# rc360detector.net
KiCad netlist of a schematic drawn in EAGLE
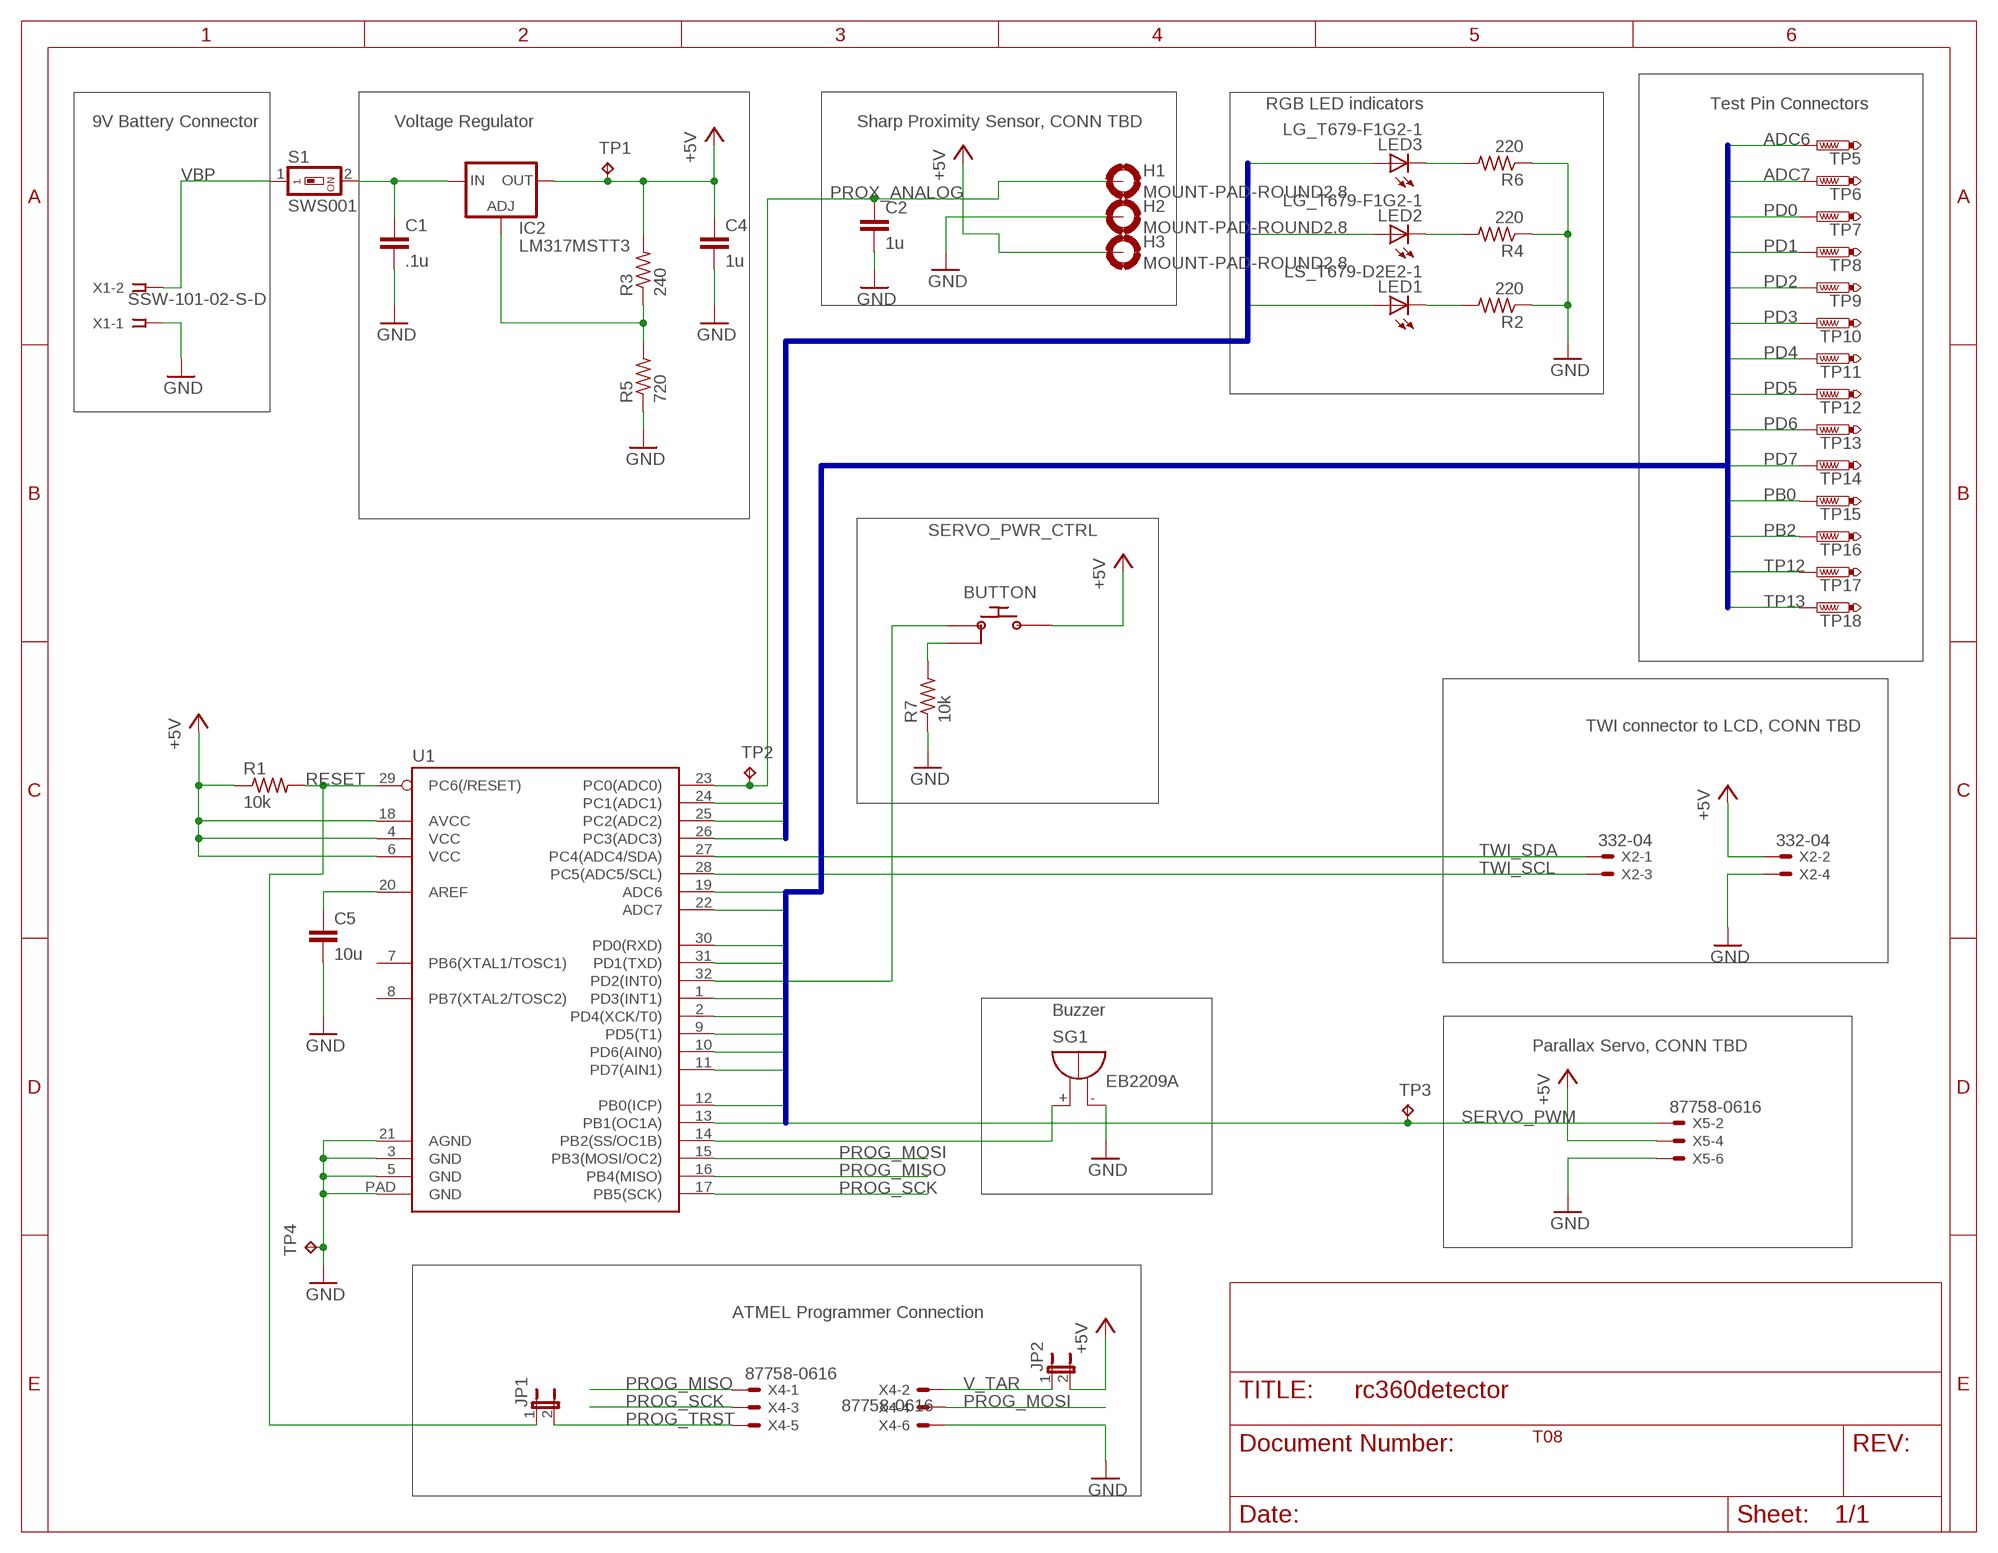
[diagram p0: schematic, sheet 1]

(export (version "E")
  (design (tool "Eeschema 10.0.6"))
  (components
    (comp (ref "BUTTON")
      (value "PR141C")
      (footprint "eagle-import:3_THROUGH_HOLE")
      (libsource (lib "eagle-import") (part "PR141C"))
    )
    (comp (ref "C1")
      (value ".1u")
      (footprint "eagle-import:C0603")
      (libsource (lib "eagle-import") (part "C-EUC0603"))
    )
    (comp (ref "C2")
      (value "1u")
      (footprint "eagle-import:C0805")
      (libsource (lib "eagle-import") (part "C-EUC0805"))
    )
    (comp (ref "C4")
      (value "1u")
      (footprint "eagle-import:C0603")
      (libsource (lib "eagle-import") (part "C-EUC0603"))
    )
    (comp (ref "C5")
      (value "10u")
      (footprint "eagle-import:C0603")
      (libsource (lib "eagle-import") (part "C-EUC0603"))
    )
    (comp (ref "H1")
      (value "MOUNT-PAD-ROUND2.8")
      (footprint "eagle-import:2,8-PAD")
      (libsource (lib "eagle-import") (part "MOUNT-PAD-ROUND2.8"))
    )
    (comp (ref "H2")
      (value "MOUNT-PAD-ROUND2.8")
      (footprint "eagle-import:2,8-PAD")
      (libsource (lib "eagle-import") (part "MOUNT-PAD-ROUND2.8"))
    )
    (comp (ref "H3")
      (value "MOUNT-PAD-ROUND2.8")
      (footprint "eagle-import:2,8-PAD")
      (libsource (lib "eagle-import") (part "MOUNT-PAD-ROUND2.8"))
    )
    (comp (ref "IC2")
      (value "LM317MSTT3")
      (footprint "eagle-import:SOT223")
      (libsource (lib "eagle-import") (part "LM317?MSTT3"))
    )
    (comp (ref "JP1")
      (value "JP1E")
      (footprint "eagle-import:JP1")
      (libsource (lib "eagle-import") (part "JP1E"))
    )
    (comp (ref "JP2")
      (value "JP1E")
      (footprint "eagle-import:JP1")
      (libsource (lib "eagle-import") (part "JP1E"))
    )
    (comp (ref "LED1")
      (value "LS_T679-D2E2-1")
      (footprint "eagle-import:PLCC2")
      (libsource (lib "eagle-import") (part "_T679-?-1D2E2LS"))
    )
    (comp (ref "LED2")
      (value "LG_T679-F1G2-1")
      (footprint "eagle-import:PLCC2")
      (libsource (lib "eagle-import") (part "_T679-?-1F1G2LG"))
    )
    (comp (ref "LED3")
      (value "LG_T679-F1G2-1")
      (footprint "eagle-import:PLCC2")
      (libsource (lib "eagle-import") (part "_T679-?-1F1G2LG"))
    )
    (comp (ref "R1")
      (value "10k")
      (footprint "eagle-import:R0603")
      (libsource (lib "eagle-import") (part "R-US_R0603"))
    )
    (comp (ref "R2")
      (value "220")
      (footprint "eagle-import:R0805")
      (libsource (lib "eagle-import") (part "R-US_R0805"))
    )
    (comp (ref "R3")
      (value "240")
      (footprint "eagle-import:R0603")
      (libsource (lib "eagle-import") (part "R-US_R0603"))
    )
    (comp (ref "R4")
      (value "220")
      (footprint "eagle-import:R0805")
      (libsource (lib "eagle-import") (part "R-US_R0805"))
    )
    (comp (ref "R5")
      (value "720")
      (footprint "eagle-import:R0603")
      (libsource (lib "eagle-import") (part "R-US_R0603"))
    )
    (comp (ref "R6")
      (value "220")
      (footprint "eagle-import:R0805")
      (libsource (lib "eagle-import") (part "R-US_R0805"))
    )
    (comp (ref "R7")
      (value "10k")
      (footprint "eagle-import:R0805")
      (libsource (lib "eagle-import") (part "R-US_R0805"))
    )
    (comp (ref "S1")
      (value "SWS001")
      (footprint "eagle-import:SMS-001")
      (libsource (lib "eagle-import") (part "SWS001"))
    )
    (comp (ref "SG1")
      (value "EB2209A")
      (footprint "eagle-import:EB2209A")
      (libsource (lib "eagle-import") (part "EB2209A"))
    )
    (comp (ref "TP1")
      (value "TPPAD1-17")
      (footprint "eagle-import:P1-17")
      (libsource (lib "eagle-import") (part "TPPAD1-17"))
    )
    (comp (ref "TP2")
      (value "TPPAD1-17")
      (footprint "eagle-import:P1-17")
      (libsource (lib "eagle-import") (part "TPPAD1-17"))
    )
    (comp (ref "TP3")
      (value "TPPAD1-17")
      (footprint "eagle-import:P1-17")
      (libsource (lib "eagle-import") (part "TPPAD1-17"))
    )
    (comp (ref "TP4")
      (value "TPPAD1-17")
      (footprint "eagle-import:P1-17")
      (libsource (lib "eagle-import") (part "TPPAD1-17"))
    )
    (comp (ref "TP5")
      (value "PTR1PAD1-20")
      (footprint "eagle-import:P1-20")
      (libsource (lib "eagle-import") (part "PTR1PAD1-20"))
    )
    (comp (ref "TP6")
      (value "PTR1PAD1-20")
      (footprint "eagle-import:P1-20")
      (libsource (lib "eagle-import") (part "PTR1PAD1-20"))
    )
    (comp (ref "TP7")
      (value "PTR1PAD1-20")
      (footprint "eagle-import:P1-20")
      (libsource (lib "eagle-import") (part "PTR1PAD1-20"))
    )
    (comp (ref "TP8")
      (value "PTR1PAD1-20")
      (footprint "eagle-import:P1-20")
      (libsource (lib "eagle-import") (part "PTR1PAD1-20"))
    )
    (comp (ref "TP9")
      (value "PTR1PAD1-20")
      (footprint "eagle-import:P1-20")
      (libsource (lib "eagle-import") (part "PTR1PAD1-20"))
    )
    (comp (ref "TP10")
      (value "PTR1PAD1-20")
      (footprint "eagle-import:P1-20")
      (libsource (lib "eagle-import") (part "PTR1PAD1-20"))
    )
    (comp (ref "TP11")
      (value "PTR1PAD1-20")
      (footprint "eagle-import:P1-20")
      (libsource (lib "eagle-import") (part "PTR1PAD1-20"))
    )
    (comp (ref "TP12")
      (value "PTR1PAD1-20")
      (footprint "eagle-import:P1-20")
      (libsource (lib "eagle-import") (part "PTR1PAD1-20"))
    )
    (comp (ref "TP13")
      (value "PTR1PAD1-20")
      (footprint "eagle-import:P1-20")
      (libsource (lib "eagle-import") (part "PTR1PAD1-20"))
    )
    (comp (ref "TP14")
      (value "PTR1PAD1-20")
      (footprint "eagle-import:P1-20")
      (libsource (lib "eagle-import") (part "PTR1PAD1-20"))
    )
    (comp (ref "TP15")
      (value "PTR1PAD1-20")
      (footprint "eagle-import:P1-20")
      (libsource (lib "eagle-import") (part "PTR1PAD1-20"))
    )
    (comp (ref "TP16")
      (value "PTR1PAD1-20")
      (footprint "eagle-import:P1-20")
      (libsource (lib "eagle-import") (part "PTR1PAD1-20"))
    )
    (comp (ref "TP17")
      (value "PTR1PAD1-20")
      (footprint "eagle-import:P1-20")
      (libsource (lib "eagle-import") (part "PTR1PAD1-20"))
    )
    (comp (ref "TP18")
      (value "PTR1PAD1-20")
      (footprint "eagle-import:P1-20")
      (libsource (lib "eagle-import") (part "PTR1PAD1-20"))
    )
    (comp (ref "U1")
      (value "ATMEGA328P_MLFMLF32")
      (footprint "eagle-import:MLF32-PAD")
      (libsource (lib "eagle-import") (part "ATMEGA328P_MLFMLF32"))
    )
    (comp (ref "X1")
      (value "SSW-101-02-S-D")
      (footprint "eagle-import:SSW-101-02-S-D")
      (libsource (lib "eagle-import") (part "SSW-101-02-S-D"))
    )
    (comp (ref "X2")
      (value "332-04")
      (footprint "eagle-import:332-04")
      (libsource (lib "eagle-import") (part "332-04"))
    )
    (comp (ref "X4")
      (value "87758-0616")
      (footprint "eagle-import:87758-0616")
      (libsource (lib "eagle-import") (part "87758-0616"))
    )
    (comp (ref "X5")
      (value "87758-0616")
      (footprint "eagle-import:87758-0616")
      (libsource (lib "eagle-import") (part "87758-0616"))
    )
  )
  (nets
    (net (code "1") (name "+5V") (class "Default")
      (node (ref "BUTTON") (pin "P$3") (pinfunction "OUT_P$3") (pintype "bidirectional"))
      (node (ref "C4") (pin "1") (pinfunction "1_1") (pintype "passive"))
      (node (ref "H3") (pin "B2,8") (pinfunction "MOUNT_B2,8") (pintype "passive"))
      (node (ref "IC2") (pin "4") (pinfunction "OUT_4") (pintype "passive"))
      (node (ref "JP2") (pin "2") (pinfunction "2_2") (pintype "passive"))
      (node (ref "R1") (pin "1") (pinfunction "1_1") (pintype "passive"))
      (node (ref "R3") (pin "2") (pinfunction "2_2") (pintype "passive"))
      (node (ref "TP1") (pin "TP") (pinfunction "TP_TP") (pintype "input"))
      (node (ref "U1") (pin "18") (pinfunction "AVCC_18") (pintype "bidirectional"))
      (node (ref "U1") (pin "4") (pinfunction "VCC_4") (pintype "bidirectional"))
      (node (ref "U1") (pin "6") (pinfunction "VCC_6") (pintype "bidirectional"))
      (node (ref "X2") (pin "2") (pinfunction "S_2") (pintype "passive"))
      (node (ref "X5") (pin "4") (pinfunction "S_4") (pintype "passive"))
    )
    (net (code "2") (name "/ADC6") (class "Default")
      (node (ref "TP5") (pin "TP") (pinfunction "TP_TP") (pintype "input"))
      (node (ref "U1") (pin "19") (pinfunction "ADC6_19") (pintype "bidirectional"))
    )
    (net (code "3") (name "/ADC7") (class "Default")
      (node (ref "TP6") (pin "TP") (pinfunction "TP_TP") (pintype "input"))
    )
    (net (code "4") (name "/LED0") (class "Default")
      (node (ref "LED1") (pin "A") (pinfunction "A_A") (pintype "passive"))
      (node (ref "U1") (pin "24") (pinfunction "PC1(ADC1)_24") (pintype "bidirectional"))
    )
    (net (code "5") (name "/LED1") (class "Default")
      (node (ref "LED2") (pin "A") (pinfunction "A_A") (pintype "passive"))
      (node (ref "U1") (pin "25") (pinfunction "PC2(ADC2)_25") (pintype "bidirectional"))
    )
    (net (code "6") (name "/LED2") (class "Default")
      (node (ref "LED3") (pin "A") (pinfunction "A_A") (pintype "passive"))
      (node (ref "U1") (pin "26") (pinfunction "PC3(ADC3)_26") (pintype "bidirectional"))
    )
    (net (code "7") (name "/PB0") (class "Default")
      (node (ref "TP15") (pin "TP") (pinfunction "TP_TP") (pintype "input"))
    )
    (net (code "8") (name "/PB2") (class "Default")
      (node (ref "TP16") (pin "TP") (pinfunction "TP_TP") (pintype "input"))
    )
    (net (code "9") (name "/PD0") (class "Default")
      (node (ref "TP7") (pin "TP") (pinfunction "TP_TP") (pintype "input"))
    )
    (net (code "10") (name "/PD1") (class "Default")
      (node (ref "TP8") (pin "TP") (pinfunction "TP_TP") (pintype "input"))
    )
    (net (code "11") (name "/PD2") (class "Default")
      (node (ref "TP9") (pin "TP") (pinfunction "TP_TP") (pintype "input"))
    )
    (net (code "12") (name "/PD3") (class "Default")
      (node (ref "TP10") (pin "TP") (pinfunction "TP_TP") (pintype "input"))
    )
    (net (code "13") (name "/PD4") (class "Default")
      (node (ref "TP11") (pin "TP") (pinfunction "TP_TP") (pintype "input"))
    )
    (net (code "14") (name "/PD5") (class "Default")
      (node (ref "TP12") (pin "TP") (pinfunction "TP_TP") (pintype "input"))
    )
    (net (code "15") (name "/PD6") (class "Default")
      (node (ref "TP13") (pin "TP") (pinfunction "TP_TP") (pintype "input"))
    )
    (net (code "16") (name "/PD7") (class "Default")
      (node (ref "TP14") (pin "TP") (pinfunction "TP_TP") (pintype "input"))
    )
    (net (code "17") (name "/PROG_MISO") (class "Default")
      (node (ref "U1") (pin "16") (pinfunction "PB4(MISO)_16") (pintype "bidirectional"))
      (node (ref "X4") (pin "1") (pinfunction "S_1") (pintype "passive"))
    )
    (net (code "18") (name "/PROG_MOSI") (class "Default")
      (node (ref "U1") (pin "15") (pinfunction "PB3(MOSI/OC2)_15") (pintype "bidirectional"))
      (node (ref "X4") (pin "4") (pinfunction "S_4") (pintype "passive"))
    )
    (net (code "19") (name "/PROG_SCK") (class "Default")
      (node (ref "U1") (pin "17") (pinfunction "PB5(SCK)_17") (pintype "bidirectional"))
      (node (ref "X4") (pin "3") (pinfunction "S_3") (pintype "passive"))
    )
    (net (code "20") (name "/PROG_TRST") (class "Default")
      (node (ref "JP1") (pin "2") (pinfunction "2_2") (pintype "passive"))
      (node (ref "X4") (pin "5") (pinfunction "S_5") (pintype "passive"))
    )
    (net (code "21") (name "/PROX_ANALOG") (class "Default")
      (node (ref "C2") (pin "1") (pinfunction "1_1") (pintype "passive"))
      (node (ref "H1") (pin "B2,8") (pinfunction "MOUNT_B2,8") (pintype "passive"))
      (node (ref "TP2") (pin "TP") (pinfunction "TP_TP") (pintype "input"))
      (node (ref "U1") (pin "23") (pinfunction "PC0(ADC0)_23") (pintype "bidirectional"))
    )
    (net (code "22") (name "/RESET") (class "Default")
      (node (ref "JP1") (pin "1") (pinfunction "1_1") (pintype "passive"))
      (node (ref "R1") (pin "2") (pinfunction "2_2") (pintype "passive"))
      (node (ref "U1") (pin "29") (pinfunction "PC6(/RESET)_29") (pintype "bidirectional"))
    )
    (net (code "23") (name "/SERVO_PWM") (class "Default")
      (node (ref "TP3") (pin "TP") (pinfunction "TP_TP") (pintype "input"))
      (node (ref "U1") (pin "13") (pinfunction "PB1(OC1A)_13") (pintype "bidirectional"))
      (node (ref "X5") (pin "2") (pinfunction "S_2") (pintype "passive"))
    )
    (net (code "24") (name "/TP12") (class "Default")
      (node (ref "TP17") (pin "TP") (pinfunction "TP_TP") (pintype "input"))
    )
    (net (code "25") (name "/TP13") (class "Default")
      (node (ref "TP18") (pin "TP") (pinfunction "TP_TP") (pintype "input"))
    )
    (net (code "26") (name "/TWI_SCL") (class "Default")
      (node (ref "U1") (pin "28") (pinfunction "PC5(ADC5/SCL)_28") (pintype "bidirectional"))
      (node (ref "X2") (pin "3") (pinfunction "S_3") (pintype "passive"))
    )
    (net (code "27") (name "/TWI_SDA") (class "Default")
      (node (ref "U1") (pin "27") (pinfunction "PC4(ADC4/SDA)_27") (pintype "bidirectional"))
      (node (ref "X2") (pin "1") (pinfunction "S_1") (pintype "passive"))
    )
    (net (code "28") (name "/VBP") (class "Default")
      (node (ref "S1") (pin "1") (pinfunction "1_1") (pintype "passive"))
      (node (ref "X1") (pin "2") (pinfunction "1_2") (pintype "passive"))
    )
    (net (code "29") (name "/V_TAR") (class "Default")
      (node (ref "JP2") (pin "1") (pinfunction "1_1") (pintype "passive"))
      (node (ref "X4") (pin "2") (pinfunction "S_2") (pintype "passive"))
    )
    (net (code "30") (name "GND") (class "Default")
      (node (ref "C1") (pin "2") (pinfunction "2_2") (pintype "passive"))
      (node (ref "C2") (pin "2") (pinfunction "2_2") (pintype "passive"))
      (node (ref "C4") (pin "2") (pinfunction "2_2") (pintype "passive"))
      (node (ref "C5") (pin "2") (pinfunction "2_2") (pintype "passive"))
      (node (ref "H2") (pin "B2,8") (pinfunction "MOUNT_B2,8") (pintype "passive"))
      (node (ref "R2") (pin "1") (pinfunction "1_1") (pintype "passive"))
      (node (ref "R4") (pin "1") (pinfunction "1_1") (pintype "passive"))
      (node (ref "R5") (pin "1") (pinfunction "1_1") (pintype "passive"))
      (node (ref "R6") (pin "1") (pinfunction "1_1") (pintype "passive"))
      (node (ref "R7") (pin "1") (pinfunction "1_1") (pintype "passive"))
      (node (ref "SG1") (pin "-") (pinfunction "-_-") (pintype "passive"))
      (node (ref "TP4") (pin "TP") (pinfunction "TP_TP") (pintype "input"))
      (node (ref "U1") (pin "21") (pinfunction "AGND_21") (pintype "bidirectional"))
      (node (ref "U1") (pin "3") (pinfunction "GND_3") (pintype "bidirectional"))
      (node (ref "U1") (pin "5") (pinfunction "GND_5") (pintype "bidirectional"))
      (node (ref "U1") (pin "PAD") (pinfunction "GND_PAD") (pintype "bidirectional"))
      (node (ref "X1") (pin "1") (pinfunction "1_1") (pintype "passive"))
      (node (ref "X2") (pin "4") (pinfunction "S_4") (pintype "passive"))
      (node (ref "X4") (pin "6") (pinfunction "S_6") (pintype "passive"))
      (node (ref "X5") (pin "6") (pinfunction "S_6") (pintype "passive"))
    )
    (net (code "31") (name "Net-(BUTTON-GND)") (class "Default")
      (node (ref "BUTTON") (pin "P$2") (pinfunction "GND_P$2") (pintype "bidirectional"))
      (node (ref "R7") (pin "2") (pinfunction "2_2") (pintype "passive"))
    )
    (net (code "32") (name "Net-(BUTTON-IN)") (class "Default")
      (node (ref "BUTTON") (pin "P$1") (pinfunction "IN_P$1") (pintype "bidirectional"))
      (node (ref "U1") (pin "32") (pinfunction "PD2(INT0)_32") (pintype "bidirectional"))
    )
    (net (code "33") (name "Net-(IC2-ADJ)") (class "Default")
      (node (ref "IC2") (pin "1") (pinfunction "ADJ_1") (pintype "input"))
      (node (ref "R3") (pin "1") (pinfunction "1_1") (pintype "passive"))
      (node (ref "R5") (pin "2") (pinfunction "2_2") (pintype "passive"))
    )
    (net (code "34") (name "Net-(IC2-IN)") (class "Default")
      (node (ref "C1") (pin "1") (pinfunction "1_1") (pintype "passive"))
      (node (ref "IC2") (pin "3") (pinfunction "IN_3") (pintype "input"))
      (node (ref "S1") (pin "2") (pinfunction "2_2") (pintype "passive"))
    )
    (net (code "35") (name "Net-(LED1-PadC)") (class "Default")
      (node (ref "LED1") (pin "C") (pinfunction "C_C") (pintype "passive"))
      (node (ref "R2") (pin "2") (pinfunction "2_2") (pintype "passive"))
    )
    (net (code "36") (name "Net-(LED2-PadC)") (class "Default")
      (node (ref "LED2") (pin "C") (pinfunction "C_C") (pintype "passive"))
      (node (ref "R4") (pin "2") (pinfunction "2_2") (pintype "passive"))
    )
    (net (code "37") (name "Net-(LED3-PadC)") (class "Default")
      (node (ref "LED3") (pin "C") (pinfunction "C_C") (pintype "passive"))
      (node (ref "R6") (pin "2") (pinfunction "2_2") (pintype "passive"))
    )
    (net (code "38") (name "Net-(U1-AREF)") (class "Default")
      (node (ref "C5") (pin "1") (pinfunction "1_1") (pintype "passive"))
      (node (ref "U1") (pin "20") (pinfunction "AREF_20") (pintype "bidirectional"))
    )
    (net (code "39") (name "Net-(U1-PB2(SS{slash}OC1B))") (class "Default")
      (node (ref "SG1") (pin "+") (pinfunction "+_+") (pintype "passive"))
      (node (ref "U1") (pin "14") (pinfunction "PB2(SS/OC1B)_14") (pintype "bidirectional"))
    )
    (net (code "40") (name "unconnected-(U1-ADC7-Pad22)") (class "Default")
      (node (ref "U1") (pin "22") (pinfunction "ADC7_22") (pintype "bidirectional"))
    )
    (net (code "41") (name "unconnected-(U1-PB0(ICP)-Pad12)") (class "Default")
      (node (ref "U1") (pin "12") (pinfunction "PB0(ICP)_12") (pintype "bidirectional"))
    )
    (net (code "42") (name "unconnected-(U1-PB6(XTAL1{slash}TOSC1)-Pad7)") (class "Default")
      (node (ref "U1") (pin "7") (pinfunction "PB6(XTAL1/TOSC1)_7") (pintype "bidirectional"))
    )
    (net (code "43") (name "unconnected-(U1-PB7(XTAL2{slash}TOSC2)-Pad8)") (class "Default")
      (node (ref "U1") (pin "8") (pinfunction "PB7(XTAL2/TOSC2)_8") (pintype "bidirectional"))
    )
    (net (code "44") (name "unconnected-(U1-PD0(RXD)-Pad30)") (class "Default")
      (node (ref "U1") (pin "30") (pinfunction "PD0(RXD)_30") (pintype "bidirectional"))
    )
    (net (code "45") (name "unconnected-(U1-PD1(TXD)-Pad31)") (class "Default")
      (node (ref "U1") (pin "31") (pinfunction "PD1(TXD)_31") (pintype "bidirectional"))
    )
    (net (code "46") (name "unconnected-(U1-PD3(INT1)-Pad1)") (class "Default")
      (node (ref "U1") (pin "1") (pinfunction "PD3(INT1)_1") (pintype "bidirectional"))
    )
    (net (code "47") (name "unconnected-(U1-PD4(XCK{slash}T0)-Pad2)") (class "Default")
      (node (ref "U1") (pin "2") (pinfunction "PD4(XCK/T0)_2") (pintype "bidirectional"))
    )
    (net (code "48") (name "unconnected-(U1-PD5(T1)-Pad9)") (class "Default")
      (node (ref "U1") (pin "9") (pinfunction "PD5(T1)_9") (pintype "bidirectional"))
    )
    (net (code "49") (name "unconnected-(U1-PD6(AIN0)-Pad10)") (class "Default")
      (node (ref "U1") (pin "10") (pinfunction "PD6(AIN0)_10") (pintype "bidirectional"))
    )
    (net (code "50") (name "unconnected-(U1-PD7(AIN1)-Pad11)") (class "Default")
      (node (ref "U1") (pin "11") (pinfunction "PD7(AIN1)_11") (pintype "bidirectional"))
    )
  )
)
